# Capteur_et_RTC.net
KiCad netlist of a schematic drawn in Altium Designer
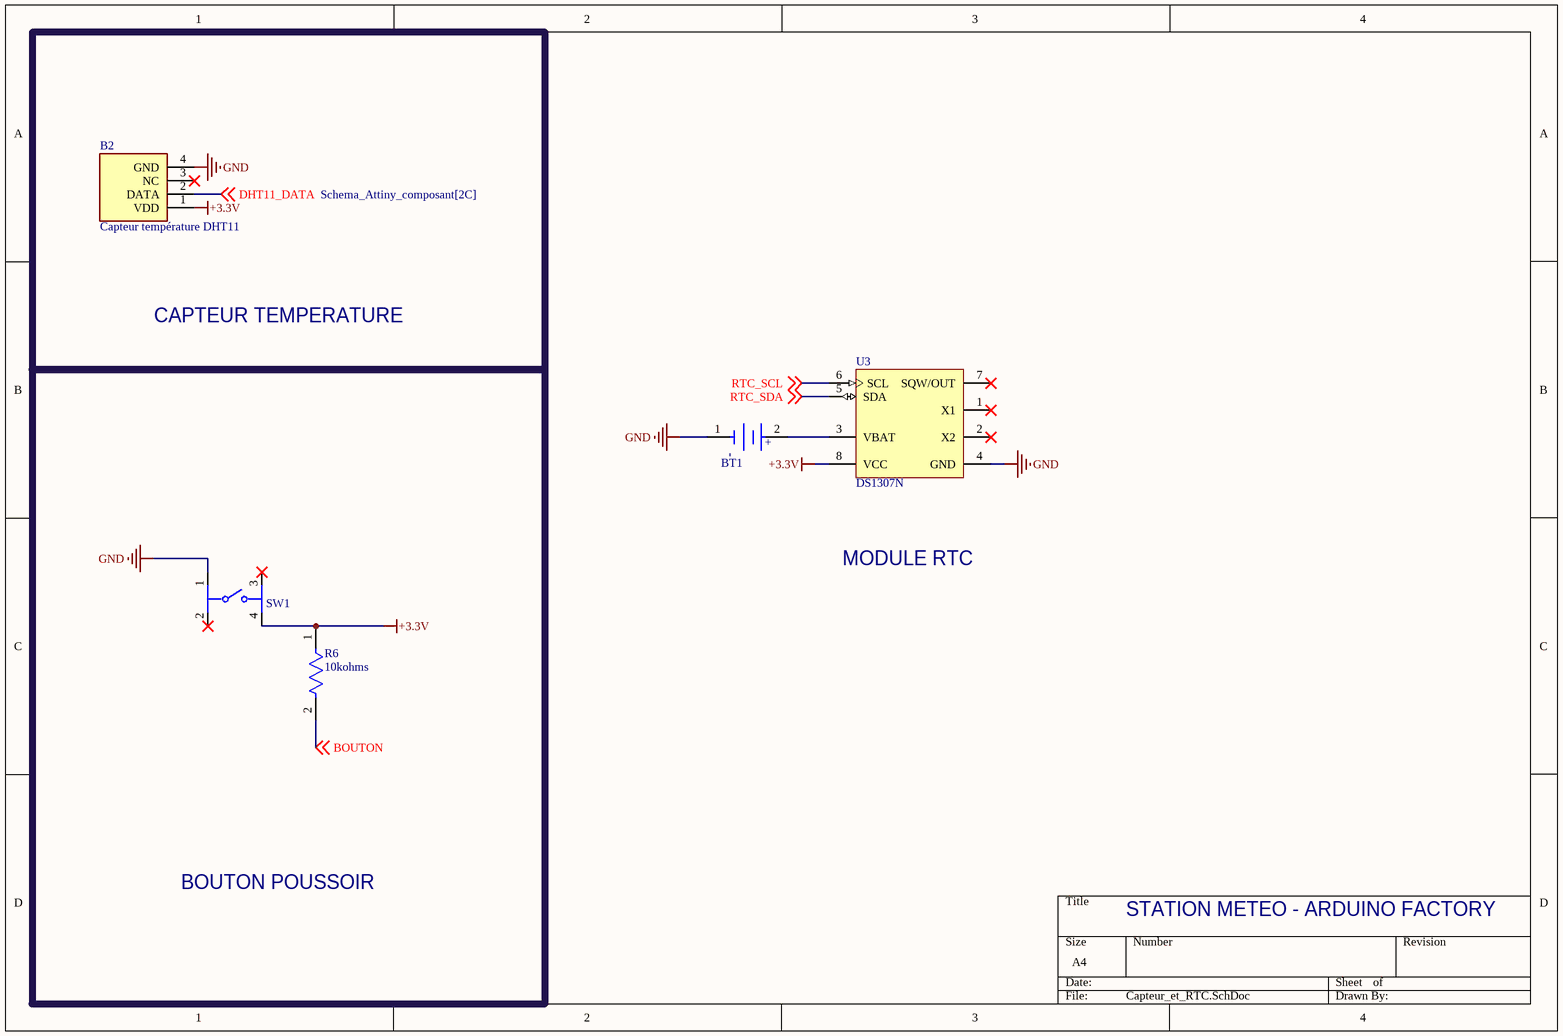
[diagram p0: Capteur_et_RTC.SchDoc]

(export (version "E")
  (design (tool "Eeschema 10.0.6"))
  (components
    (comp (ref "B2")
      (value "Capteur température DHT11")
      (footprint "386")
      (description "Adafruit Accessories DHT11 Basic Temp Humidity Sensor")
      (fields (field (name "MANUFACTURER_PART_NUMBER") "386") (field (name "MOUSER PART NUMBER") "485-386"))
      (libsource (lib "386") (part "386"))
    )
    (comp (ref "BT1")
      (value "3034TR")
      (footprint "Keystone_0_MFG")
      (libsource (lib "Batt_Keystone_3034TR_eec") (part "3034TR"))
    )
    (comp (ref "R6")
      (value "10kohms")
      (footprint "Stackpole_Electronics_Inc._CF14JT1K00_0")
      (libsource (lib "Res_Yageo_MF0207FTE52-10K_eec") (part "MF0207FTE52-10K"))
    )
    (comp (ref "SW1")
      (value "1825910-2")
      (footprint "TE_0_0")
      (libsource (lib "Switch_TE_1825910-2_eec") (part "1825910-2"))
    )
    (comp (ref "U3")
      (value "DS1307N")
      (footprint "P8-2")
      (description "64 x 8, Serial, I2C Real-Time Clock, 5.0V, 8-Pin PDIP, -40 to 85 degC")
      (libsource (lib "Maxim_DS1307N") (part "DS1307N"))
    )
  )
  (nets
    (net (code "1") (name "+3.3V") (class "Default")
      (node (ref "B2") (pin "1") (pinfunction "VDD_1") (pintype "passive"))
      (node (ref "R6") (pin "1") (pinfunction "1_1") (pintype "passive"))
      (node (ref "SW1") (pin "4") (pinfunction "4_4") (pintype "passive"))
      (node (ref "U3") (pin "8") (pinfunction "VCC_8") (pintype "power_in"))
    )
    (net (code "2") (name "BOUTON") (class "Default")
      (node (ref "R6") (pin "2") (pinfunction "2_2") (pintype "passive"))
    )
    (net (code "3") (name "DHT11_DATA") (class "Default")
      (node (ref "B2") (pin "2") (pinfunction "DATA_2") (pintype "passive"))
    )
    (net (code "4") (name "GND") (class "Default")
      (node (ref "B2") (pin "4") (pinfunction "GND_4") (pintype "passive"))
      (node (ref "BT1") (pin "1") (pinfunction "C_1") (pintype "passive"))
      (node (ref "SW1") (pin "1") (pinfunction "1_1") (pintype "passive"))
      (node (ref "U3") (pin "4") (pinfunction "GND_4") (pintype "power_in"))
    )
    (net (code "5") (name "Net-(BT1-A)") (class "Default")
      (node (ref "BT1") (pin "2") (pinfunction "A_2") (pintype "passive"))
      (node (ref "U3") (pin "3") (pinfunction "VBAT_3") (pintype "power_in"))
    )
    (net (code "6") (name "RTC_SCL") (class "Default")
      (node (ref "U3") (pin "6") (pinfunction "SCL_6") (pintype "input"))
    )
    (net (code "7") (name "RTC_SDA") (class "Default")
      (node (ref "U3") (pin "5") (pinfunction "SDA_5") (pintype "bidirectional"))
    )
    (net (code "8") (name "unconnected-(B2-NC-Pad3)") (class "Default")
      (node (ref "B2") (pin "3") (pinfunction "NC_3") (pintype "passive+no_connect"))
    )
    (net (code "9") (name "unconnected-(SW1-Pad2)") (class "Default")
      (node (ref "SW1") (pin "2") (pinfunction "2_2") (pintype "passive+no_connect"))
    )
    (net (code "10") (name "unconnected-(SW1-Pad3)") (class "Default")
      (node (ref "SW1") (pin "3") (pinfunction "3_3") (pintype "passive+no_connect"))
    )
    (net (code "11") (name "unconnected-(U3-SQW{slash}OUT-Pad7)") (class "Default")
      (node (ref "U3") (pin "7") (pinfunction "SQW/OUT_7") (pintype "open_collector+no_connect"))
    )
    (net (code "12") (name "unconnected-(U3-X1-Pad1)") (class "Default")
      (node (ref "U3") (pin "1") (pinfunction "X1_1") (pintype "passive+no_connect"))
    )
    (net (code "13") (name "unconnected-(U3-X2-Pad2)") (class "Default")
      (node (ref "U3") (pin "2") (pinfunction "X2_2") (pintype "passive+no_connect"))
    )
  )
)
